# Sensor_Board.net
KiCad netlist of a schematic drawn in Altium Designer
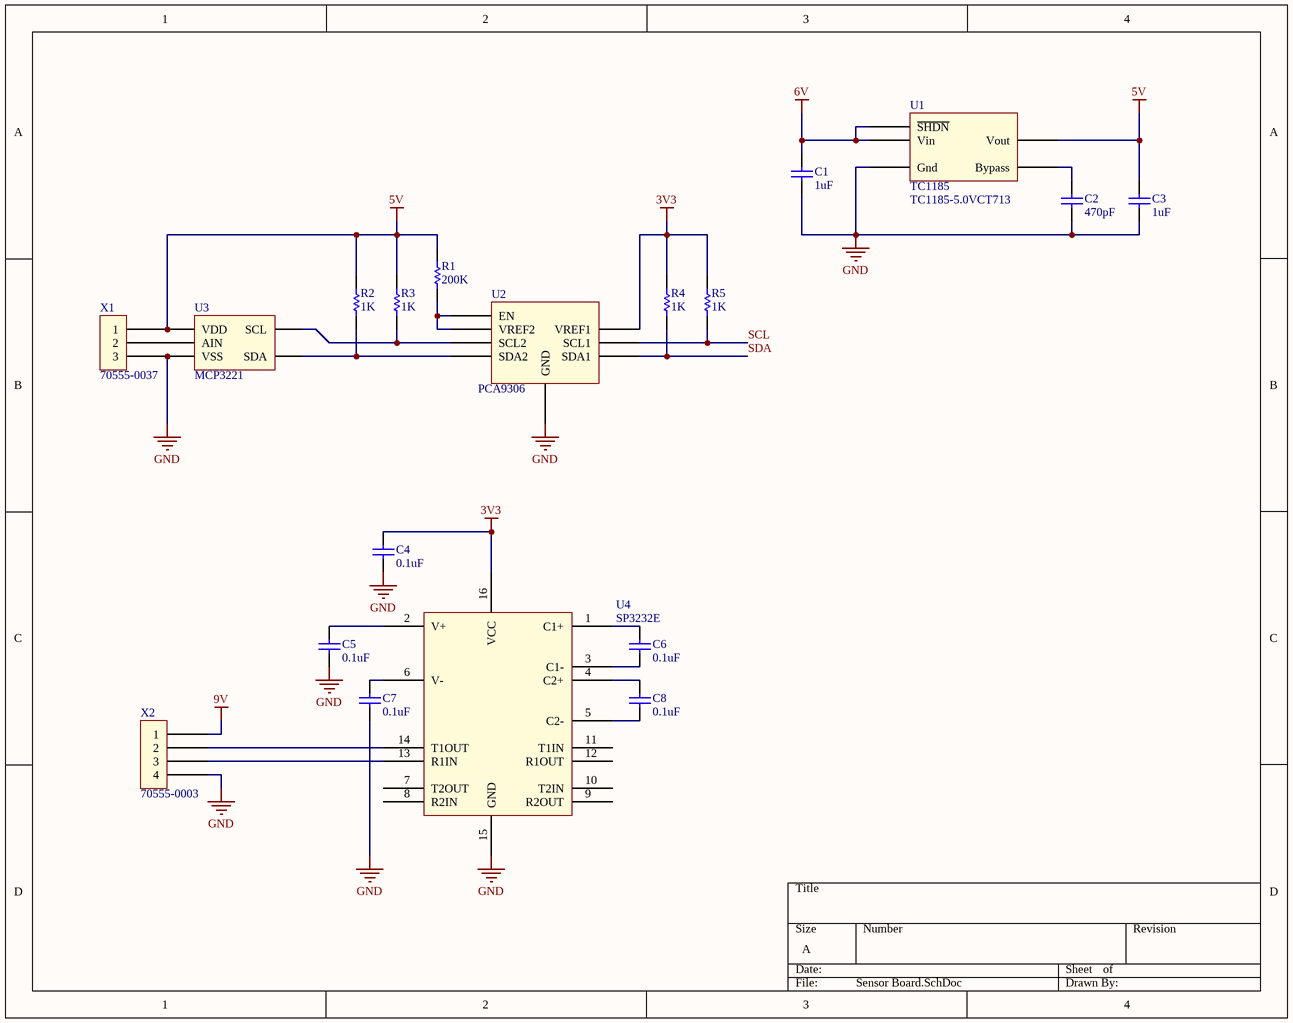
[diagram p0: Sensor Board.SchDoc]

(export (version "E")
  (design (tool "Eeschema 10.0.6"))
  (components
    (comp (ref "C1")
      (value "1uF")
      (footprint "C0603")
      (description "Unpolarized Capacitor")
      (fields (field (name "Comment") "Cap"))
      (libsource (lib "URC_Lib") (part "Cap"))
    )
    (comp (ref "C2")
      (value "470pF")
      (footprint "C0603")
      (description "Unpolarized Capacitor")
      (fields (field (name "Comment") "Cap"))
      (libsource (lib "URC_Lib") (part "Cap"))
    )
    (comp (ref "C3")
      (value "1uF")
      (footprint "C0603")
      (description "Unpolarized Capacitor")
      (fields (field (name "Comment") "Cap"))
      (libsource (lib "URC_Lib") (part "Cap"))
    )
    (comp (ref "C4")
      (value "0.1uF")
      (footprint "C0805")
      (description "Unpolarized Capacitor")
      (fields (field (name "Comment") "Cap"))
      (libsource (lib "URC") (part "Cap"))
    )
    (comp (ref "C5")
      (value "0.1uF")
      (footprint "C0805")
      (description "Unpolarized Capacitor")
      (fields (field (name "Comment") "Cap"))
      (libsource (lib "URC") (part "Cap"))
    )
    (comp (ref "C6")
      (value "0.1uF")
      (footprint "C0805")
      (description "Unpolarized Capacitor")
      (fields (field (name "Comment") "Cap"))
      (libsource (lib "URC") (part "Cap"))
    )
    (comp (ref "C7")
      (value "0.1uF")
      (footprint "C0805")
      (description "Unpolarized Capacitor")
      (fields (field (name "Comment") "Cap"))
      (libsource (lib "URC") (part "Cap"))
    )
    (comp (ref "C8")
      (value "0.1uF")
      (footprint "C0805")
      (description "Unpolarized Capacitor")
      (fields (field (name "Comment") "Cap"))
      (libsource (lib "URC") (part "Cap"))
    )
    (comp (ref "R1")
      (value "200K")
      (footprint "R0603")
      (description "Resistor")
      (fields (field (name "TOLERANCE") "5%"))
      (libsource (lib "URC_Lib") (part "Res"))
    )
    (comp (ref "R2")
      (value "1K")
      (footprint "R0603")
      (description "Resistor")
      (fields (field (name "TOLERANCE") "5%"))
      (libsource (lib "URC_Lib") (part "Res"))
    )
    (comp (ref "R3")
      (value "1K")
      (footprint "R0603")
      (description "Resistor")
      (fields (field (name "TOLERANCE") "5%"))
      (libsource (lib "URC_Lib") (part "Res"))
    )
    (comp (ref "R4")
      (value "1K")
      (footprint "R0603")
      (description "Resistor")
      (fields (field (name "TOLERANCE") "5%"))
      (libsource (lib "URC_Lib") (part "Res"))
    )
    (comp (ref "R5")
      (value "1K")
      (footprint "R0603")
      (description "Resistor")
      (fields (field (name "TOLERANCE") "5%"))
      (libsource (lib "URC_Lib") (part "Res"))
    )
    (comp (ref "U1")
      (value "TC1185")
      (footprint "TC1185-SOT23-5")
      (description "TC1185 LDO Regulator")
      (fields (field (name "PART NUMBER") "TC1185-5.0VCT713"))
      (libsource (lib "URC") (part "TC1185"))
    )
    (comp (ref "U2")
      (value "PCA9306")
      (footprint "PCA9306-SO8")
      (description "PCA9306, Bidirectional level translator")
      (libsource (lib "URC") (part "PCA9306"))
    )
    (comp (ref "U3")
      (value "MCP3221")
      (footprint "MCP3221-SOT23-5")
      (description "MCP3221, 12 bit ADC, I2C")
      (libsource (lib "URC") (part "MCP3221"))
    )
    (comp (ref "U4")
      (value "SP3232E")
      (footprint "SP3232E-SSOP16")
      (description "RS232 Transceiver")
      (libsource (lib "URC") (part "SP3232E"))
    )
    (comp (ref "X1")
      (value "70555-0037")
      (footprint "70555-0037")
      (description "Molex, C-Grid SL 70555, 3 Pin")
      (libsource (lib "URC") (part "70555-0037"))
    )
    (comp (ref "X2")
      (value "70555-0003")
      (footprint "70555-0003")
      (description "Molex, C-Grid SL 70555, 4 Pin")
      (libsource (lib "URC_Lib") (part "70555-0003"))
    )
  )
  (nets
    (net (code "1") (name "/SCL") (class "Default")
      (node (ref "R5") (pin "1") (pinfunction "1_1") (pintype "passive"))
      (node (ref "U2") (pin "SCL1") (pinfunction "SCL1_SCL1") (pintype "passive"))
    )
    (net (code "2") (name "/SDA") (class "Default")
      (node (ref "R4") (pin "1") (pinfunction "1_1") (pintype "passive"))
      (node (ref "U2") (pin "SDA1") (pinfunction "SDA1_SDA1") (pintype "passive"))
    )
    (net (code "3") (name "3V3") (class "Default")
      (node (ref "C4") (pin "1") (pinfunction "1_1") (pintype "passive"))
      (node (ref "R4") (pin "2") (pinfunction "2_2") (pintype "passive"))
      (node (ref "R5") (pin "2") (pinfunction "2_2") (pintype "passive"))
      (node (ref "U2") (pin "VREF1") (pinfunction "VREF1_VREF1") (pintype "passive"))
      (node (ref "U4") (pin "16") (pinfunction "VCC_16") (pintype "passive"))
    )
    (net (code "4") (name "5V") (class "Default")
      (node (ref "C3") (pin "1") (pinfunction "1_1") (pintype "passive"))
      (node (ref "R1") (pin "2") (pinfunction "2_2") (pintype "passive"))
      (node (ref "R2") (pin "2") (pinfunction "2_2") (pintype "passive"))
      (node (ref "R3") (pin "2") (pinfunction "2_2") (pintype "passive"))
      (node (ref "U1") (pin "VOUT") (pinfunction "Vout_VOUT") (pintype "passive"))
      (node (ref "U3") (pin "VDD") (pinfunction "VDD_VDD") (pintype "passive"))
      (node (ref "X1") (pin "1") (pinfunction "1_1") (pintype "passive"))
    )
    (net (code "5") (name "6V") (class "Default")
      (node (ref "C1") (pin "1") (pinfunction "1_1") (pintype "passive"))
      (node (ref "U1") (pin "SHDN") (pinfunction "~{SHDN}_SHDN") (pintype "passive"))
      (node (ref "U1") (pin "VIN") (pinfunction "Vin_VIN") (pintype "passive"))
    )
    (net (code "6") (name "9V") (class "Default")
      (node (ref "X2") (pin "1") (pinfunction "1_1") (pintype "passive"))
    )
    (net (code "7") (name "GND") (class "Default")
      (node (ref "C1") (pin "2") (pinfunction "2_2") (pintype "passive"))
      (node (ref "C2") (pin "2") (pinfunction "2_2") (pintype "passive"))
      (node (ref "C3") (pin "2") (pinfunction "2_2") (pintype "passive"))
      (node (ref "C4") (pin "2") (pinfunction "2_2") (pintype "passive"))
      (node (ref "C5") (pin "2") (pinfunction "2_2") (pintype "passive"))
      (node (ref "C7") (pin "2") (pinfunction "2_2") (pintype "passive"))
      (node (ref "U1") (pin "GND") (pinfunction "Gnd_GND") (pintype "passive"))
      (node (ref "U2") (pin "GND") (pinfunction "GND_GND") (pintype "passive"))
      (node (ref "U3") (pin "VSS") (pinfunction "VSS_VSS") (pintype "passive"))
      (node (ref "U4") (pin "15") (pinfunction "GND_15") (pintype "passive"))
      (node (ref "X1") (pin "3") (pinfunction "3_3") (pintype "passive"))
      (node (ref "X2") (pin "4") (pinfunction "4_4") (pintype "passive"))
    )
    (net (code "8") (name "Net-(R1-Pad1)") (class "Default")
      (node (ref "R1") (pin "1") (pinfunction "1_1") (pintype "passive"))
      (node (ref "U2") (pin "EN") (pinfunction "EN_EN") (pintype "passive"))
      (node (ref "U2") (pin "VREF2") (pinfunction "VREF2_VREF2") (pintype "passive"))
    )
    (net (code "9") (name "Net-(R2-Pad1)") (class "Default")
      (node (ref "R2") (pin "1") (pinfunction "1_1") (pintype "passive"))
      (node (ref "U2") (pin "SDA2") (pinfunction "SDA2_SDA2") (pintype "passive"))
      (node (ref "U3") (pin "SDA") (pinfunction "SDA_SDA") (pintype "passive"))
    )
    (net (code "10") (name "Net-(R3-Pad1)") (class "Default")
      (node (ref "R3") (pin "1") (pinfunction "1_1") (pintype "passive"))
      (node (ref "U2") (pin "SCL2") (pinfunction "SCL2_SCL2") (pintype "passive"))
      (node (ref "U3") (pin "SCL") (pinfunction "SCL_SCL") (pintype "passive"))
    )
    (net (code "11") (name "Net-(U1-Bypass)") (class "Default")
      (node (ref "C2") (pin "1") (pinfunction "1_1") (pintype "passive"))
      (node (ref "U1") (pin "BYPASS") (pinfunction "Bypass_BYPASS") (pintype "passive"))
    )
    (net (code "12") (name "Net-(U3-PadAIN)") (class "Default")
      (node (ref "U3") (pin "AIN") (pinfunction "AIN_AIN") (pintype "passive"))
      (node (ref "X1") (pin "2") (pinfunction "2_2") (pintype "passive"))
    )
    (net (code "13") (name "Net-(U4-C1+)") (class "Default")
      (node (ref "C6") (pin "1") (pinfunction "1_1") (pintype "passive"))
      (node (ref "U4") (pin "1") (pinfunction "C1+_1") (pintype "passive"))
    )
    (net (code "14") (name "Net-(U4-C1-)") (class "Default")
      (node (ref "C6") (pin "2") (pinfunction "2_2") (pintype "passive"))
      (node (ref "U4") (pin "3") (pinfunction "C1-_3") (pintype "passive"))
    )
    (net (code "15") (name "Net-(U4-C2+)") (class "Default")
      (node (ref "C8") (pin "1") (pinfunction "1_1") (pintype "passive"))
      (node (ref "U4") (pin "4") (pinfunction "C2+_4") (pintype "passive"))
    )
    (net (code "16") (name "Net-(U4-C2-)") (class "Default")
      (node (ref "C8") (pin "2") (pinfunction "2_2") (pintype "passive"))
      (node (ref "U4") (pin "5") (pinfunction "C2-_5") (pintype "passive"))
    )
    (net (code "17") (name "Net-(U4-R1IN)") (class "Default")
      (node (ref "U4") (pin "13") (pinfunction "R1IN_13") (pintype "passive"))
      (node (ref "X2") (pin "3") (pinfunction "3_3") (pintype "passive"))
    )
    (net (code "18") (name "Net-(U4-T1OUT)") (class "Default")
      (node (ref "U4") (pin "14") (pinfunction "T1OUT_14") (pintype "passive"))
      (node (ref "X2") (pin "2") (pinfunction "2_2") (pintype "passive"))
    )
    (net (code "19") (name "Net-(U4-V+)") (class "Default")
      (node (ref "C5") (pin "1") (pinfunction "1_1") (pintype "passive"))
      (node (ref "U4") (pin "2") (pinfunction "V+_2") (pintype "passive"))
    )
    (net (code "20") (name "Net-(U4-V-)") (class "Default")
      (node (ref "C7") (pin "1") (pinfunction "1_1") (pintype "passive"))
      (node (ref "U4") (pin "6") (pinfunction "V-_6") (pintype "passive"))
    )
    (net (code "21") (name "unconnected-(U4-R1OUT-Pad12)") (class "Default")
      (node (ref "U4") (pin "12") (pinfunction "R1OUT_12") (pintype "passive"))
    )
    (net (code "22") (name "unconnected-(U4-R2IN-Pad8)") (class "Default")
      (node (ref "U4") (pin "8") (pinfunction "R2IN_8") (pintype "passive"))
    )
    (net (code "23") (name "unconnected-(U4-R2OUT-Pad9)") (class "Default")
      (node (ref "U4") (pin "9") (pinfunction "R2OUT_9") (pintype "passive"))
    )
    (net (code "24") (name "unconnected-(U4-T1IN-Pad11)") (class "Default")
      (node (ref "U4") (pin "11") (pinfunction "T1IN_11") (pintype "passive"))
    )
    (net (code "25") (name "unconnected-(U4-T2IN-Pad10)") (class "Default")
      (node (ref "U4") (pin "10") (pinfunction "T2IN_10") (pintype "passive"))
    )
    (net (code "26") (name "unconnected-(U4-T2OUT-Pad7)") (class "Default")
      (node (ref "U4") (pin "7") (pinfunction "T2OUT_7") (pintype "passive"))
    )
  )
)
